# 07_MCU_POWER.net
KiCad netlist of a schematic drawn in Altium Designer
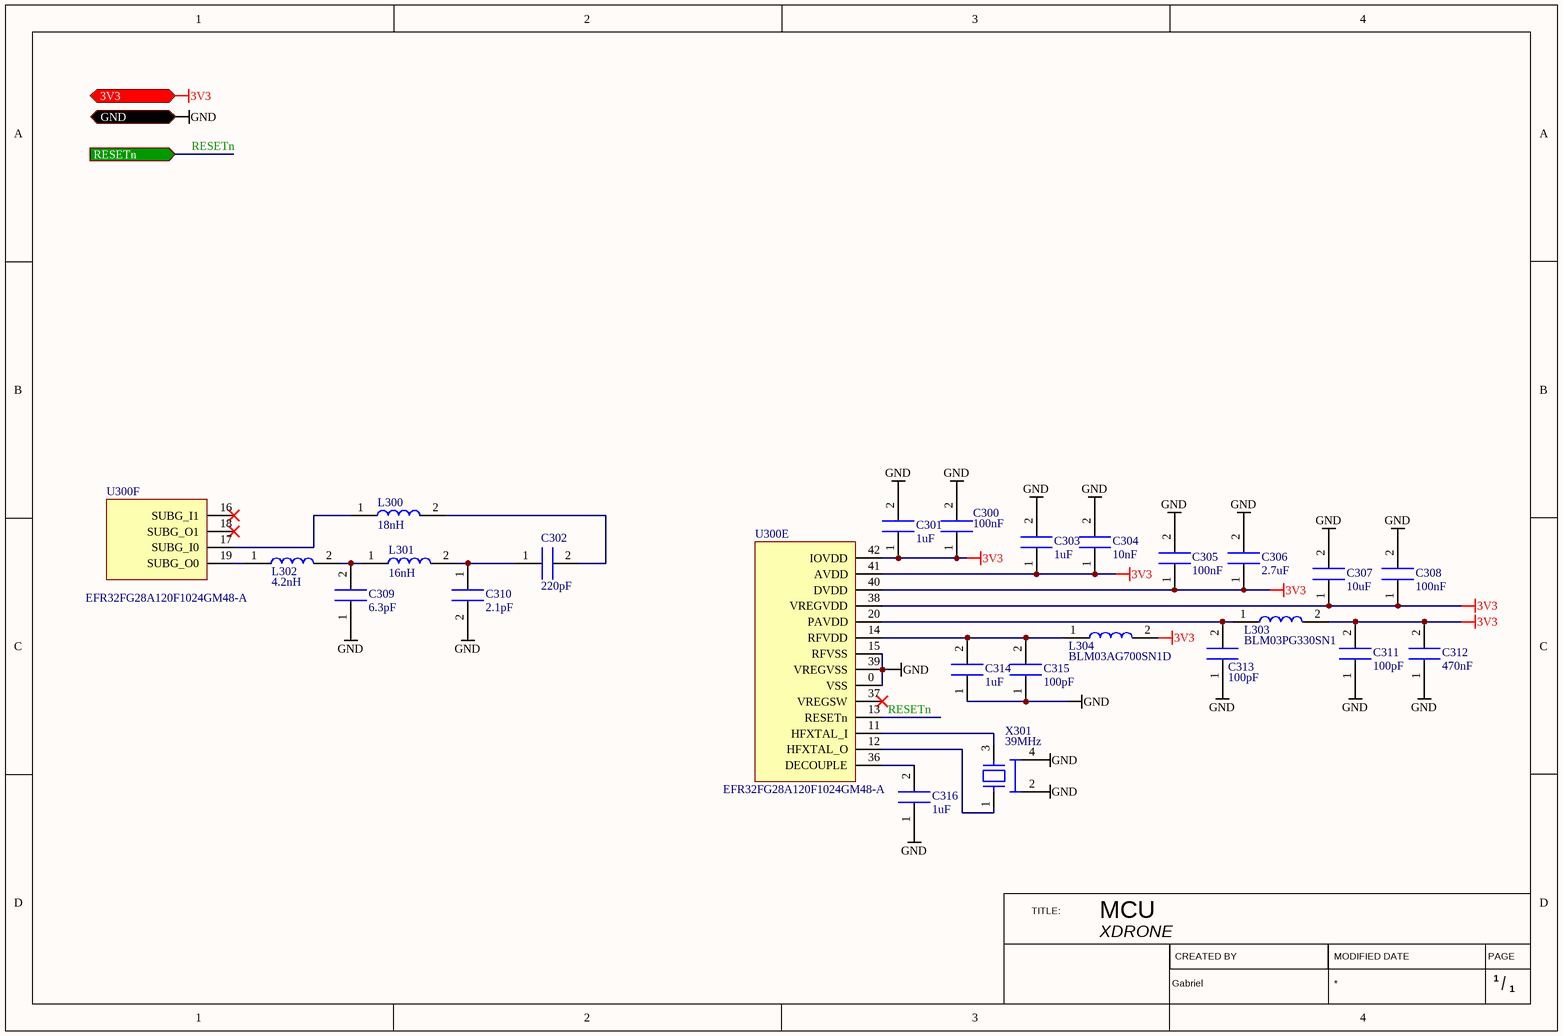
[diagram p0: 07_MCU_POWER.SchDoc]

(export (version "E")
  (design (tool "Eeschema 10.0.6"))
  (components
    (comp (ref "C300")
      (value "100nF")
      (footprint "CAP_0402")
      (description "CAPACITOR 100nF 10% X7R 0402")
      (fields (field (name "TOLERANCE") "10%") (field (name "MANUFACTURER") "MURATA"))
      (libsource (lib "Capacitors") (part "100nF_10%_16V_0402_GRM155R71C104KA88J"))
    )
    (comp (ref "C301")
      (value "1uF")
      (footprint "CAP_0402")
      (description "CAPACITOR 1uF 10% X5R 0402")
      (fields (field (name "TOLERANCE") "10%") (field (name "MANUFACTURER") "MURATA"))
      (libsource (lib "Capacitors") (part "1uF_10%_35V_0402_GRM155R6YA105KE11J"))
    )
    (comp (ref "C302")
      (value "220pF")
      (footprint "CAP_0805")
      (description "CAP 220pF 5% 50V 0805 C0G,NP0")
      (fields (field (name "TOLERANCE") "5%") (field (name "MANUFACTURER") "JOHANSON TECHLONOGY"))
      (libsource (lib "Capacitors") (part "220pF_5%_50V_0805_C0G,NP0_QSCT251Q221J1GV001E"))
    )
    (comp (ref "C303")
      (value "1uF")
      (footprint "CAP_0402")
      (description "CAPACITOR 1uF 10% X5R 0402")
      (fields (field (name "TOLERANCE") "10%") (field (name "MANUFACTURER") "MURATA"))
      (libsource (lib "Capacitors") (part "1uF_10%_35V_0402_GRM155R6YA105KE11J"))
    )
    (comp (ref "C304")
      (value "10nF")
      (footprint "CAP_0402")
      (description "CAPACITOR 10nF 10% 6.3V 0402 CC0402KRX7R5BB103")
      (fields (field (name "TOLERANCE") "10%") (field (name "MANUFACTURER") "YAGEO"))
      (libsource (lib "Capacitors") (part "10nF_10%_6.3V_0402_CC0402KRX7R5BB103"))
    )
    (comp (ref "C305")
      (value "100nF")
      (footprint "CAP_0402")
      (description "CAPACITOR 100nF 10% X7R 0402")
      (fields (field (name "TOLERANCE") "10%") (field (name "MANUFACTURER") "MURATA"))
      (libsource (lib "Capacitors") (part "100nF_10%_16V_0402_GRM155R71C104KA88J"))
    )
    (comp (ref "C306")
      (value "2.7uF")
      (footprint "CAP_0805")
      (description "CAP 2.7uF 10% 10V 0805 X5R C0805C275K8PAC7800")
      (fields (field (name "TOLERANCE") "10%") (field (name "MANUFACTURER") "KEMET"))
      (libsource (lib "Capacitors") (part "2.7uF_10%_10V_0805_X5R_C0805C275K8PAC7800"))
    )
    (comp (ref "C307")
      (value "10uF")
      (footprint "CAP_0402")
      (description "CAPACITOR 10uF 20% 6.3V 0402 GRM155R60J106ME05D")
      (fields (field (name "TOLERANCE") "20%") (field (name "MANUFACTURER") "MURATA"))
      (libsource (lib "Capacitors") (part "10uF 20% 6.3V 0402 GRM155R60J106ME05D"))
    )
    (comp (ref "C308")
      (value "100nF")
      (footprint "CAP_0402")
      (description "CAPACITOR 100nF 10% X7R 0402")
      (fields (field (name "TOLERANCE") "10%") (field (name "MANUFACTURER") "MURATA"))
      (libsource (lib "Capacitors") (part "100nF_10%_16V_0402_GRM155R71C104KA88J"))
    )
    (comp (ref "C309")
      (value "6.3pF")
      (footprint "CAP_0402")
      (description "CAPACITOR 6.3pF 1.5% 50V 0402 CBR04C639B5GAC")
      (fields (field (name "TOLERANCE") "1.5%") (field (name "MANUFACTURER") "KEMET"))
      (libsource (lib "Capacitors") (part "6.3pF_1.5%_50V_0402_CBR04C639B5GAC"))
    )
    (comp (ref "C310")
      (value "2.1pF")
      (footprint "CAP_0402")
      (description "CAPACITOR 2.1pF 5% 50V 0402 GJM1555C1H2R1BB01D")
      (fields (field (name "TOLERANCE") "5%") (field (name "MANUFACTURER") "MURATA"))
      (libsource (lib "Capacitors") (part "2.1pF_5%_50V_0402_GJM1555C1H2R1BB01D"))
    )
    (comp (ref "C311")
      (value "100pF")
      (footprint "CAP_0402")
      (description "CAPACITOR 100pF 5% 50V 0402 CC0402JRNPO9BN101")
      (fields (field (name "TOLERANCE") "5%") (field (name "MANUFACTURER") "YAGEO"))
      (libsource (lib "Capacitors") (part "100pF_5%_50V_0402_CC0402JRNPO9BN101"))
    )
    (comp (ref "C312")
      (value "470nF")
      (footprint "CAP_0402")
      (description "CAPACITOR 470nF 10% 6.3V 0402 GCM1555C1H101JA16D")
      (fields (field (name "TOLERANCE") "5%") (field (name "MANUFACTURER") "MURATA"))
      (libsource (lib "Capacitors") (part "470nF_10%_6.3V_0402_GCM1555C1H101JA16D"))
    )
    (comp (ref "C313")
      (value "100pF")
      (footprint "CAP_0402")
      (description "CAPACITOR 100pF 5% 50V 0402 CC0402JRNPO9BN101")
      (fields (field (name "TOLERANCE") "5%") (field (name "MANUFACTURER") "YAGEO"))
      (libsource (lib "Capacitors") (part "100pF_5%_50V_0402_CC0402JRNPO9BN101"))
    )
    (comp (ref "C314")
      (value "1uF")
      (footprint "CAP_0402")
      (description "CAPACITOR 1uF 10% X5R 0402")
      (fields (field (name "TOLERANCE") "10%") (field (name "MANUFACTURER") "MURATA"))
      (libsource (lib "Capacitors") (part "1uF_10%_35V_0402_GRM155R6YA105KE11J"))
    )
    (comp (ref "C315")
      (value "100pF")
      (footprint "CAP_0402")
      (description "CAPACITOR 100pF 5% 50V 0402 CC0402JRNPO9BN101")
      (fields (field (name "TOLERANCE") "5%") (field (name "MANUFACTURER") "YAGEO"))
      (libsource (lib "Capacitors") (part "100pF_5%_50V_0402_CC0402JRNPO9BN101"))
    )
    (comp (ref "C316")
      (value "1uF")
      (footprint "CAP_0402")
      (description "CAPACITOR 1uF 10% X5R 0402")
      (fields (field (name "TOLERANCE") "10%") (field (name "MANUFACTURER") "MURATA"))
      (libsource (lib "Capacitors") (part "1uF_10%_35V_0402_GRM155R6YA105KE11J"))
    )
    (comp (ref "L300")
      (value "18nH")
      (footprint "RF_IND_0402")
      (description "INDUCTOR 18nH 2% 400mA LQG15HS18NG02D")
      (fields (field (name "TOLERANCE") "2%") (field (name "MANUFACTURER") "MURATA"))
      (libsource (lib "Inductors") (part "18nH_2%_400mA_LQG15HS18NG02D"))
    )
    (comp (ref "L301")
      (value "16nH")
      (footprint "RF_IND_0402")
      (description "INDUCTOR 16nH 3% 400mA MLG1005S16NHT000")
      (fields (field (name "TOLERANCE") "3%") (field (name "MANUFACTURER") "TDK"))
      (libsource (lib "Inductors") (part "16nH_3%_400mA_MLG1005S16NHT000"))
    )
    (comp (ref "L302")
      (value "4.2nH")
      (footprint "RF_IND_0402")
      (description "INDUCTOR 4.2nH 5% 1.8A LQW15AN4N2C8ZD")
      (fields (field (name "TOLERANCE") "5%") (field (name "MANUFACTURER") "MURATA"))
      (libsource (lib "Inductors") (part "4.2nH_5%_1.8A_LQW15AN4N2C8ZD"))
    )
    (comp (ref "L303")
      (value "52nH_25%_750mA_BLM03PG330SN1")
      (footprint "IND_0201")
      (description "INDUCTOR 52uH 25% 750mA BLM03PG330SN1")
      (fields
        (field (name "TOLERANCE") "25%")
        (field (name "MANUFACTURER") "MURATA")
        (field (name "MANUFACTURER REFERENCE") "BLM03PG330SN1")
      )
      (libsource (lib "Inductors") (part "52nH_25%_750mA_BLM03PG330SN1"))
    )
    (comp (ref "L304")
      (value "110nH_50%_200mA_BLM03AG700SN1D")
      (footprint "IND_0201")
      (description "INDUCTOR 110nH 50% 200mA BLM03AG700SN1D")
      (fields
        (field (name "TOLERANCE") "50%")
        (field (name "MANUFACTURER") "MURATA")
        (field (name "MANUFACTURER REFERENCE") "BLM03AG700SN1D")
      )
      (libsource (lib "Inductors") (part "110nH 50% 200mA BLM03AG700SN1D"))
    )
    (comp (ref "U300")
      (value "MCU_1MB_256kB_EFR32FG28A120F1024GM48-A")
      (footprint "QFN48 0606")
      (description "MCU 1MB 256kB EFR32FG28A120F1024GM48-A")
      (fields
        (field (name "MANUFACTURER") "SILICON LABS")
        (field (name "MANUFACTURER REFERENCE") "EFR32FG28A120F1024GM48-A")
      )
      (libsource (lib "Semiconductor") (part "MCU_1MB_256kB_EFR32FG28A120F1024GM48-A"))
    )
    (comp (ref "X301")
      (value "QUARTZ_39MHz_10ppm_ECS-390-10-37B-CKM-TR")
      (footprint "QUARTZ_4-SMD")
      (description "QUARTZ 39MHz 10ppm ECS-390-10-37B-CKM-TR")
      (fields
        (field (name "MANUFACTURER") "ECS")
        (field (name "TOLERANCE") "10 ppm")
        (field (name "FREQUENCY") "39MHz")
      )
      (libsource (lib "Oscillators") (part "QUARTZ_39MHz_10ppm_ECS-390-10-37B-CKM-TR"))
    )
  )
  (nets
    (net (code "1") (name "/RESETn") (class "Default")
      (node (ref "U300") (pin "13") (pinfunction "RESETn_13") (pintype "passive"))
    )
    (net (code "2") (name "3V3") (class "Default")
      (node (ref "C300") (pin "1") (pinfunction "1_1") (pintype "passive"))
      (node (ref "C301") (pin "1") (pinfunction "1_1") (pintype "passive"))
      (node (ref "C303") (pin "1") (pinfunction "1_1") (pintype "passive"))
      (node (ref "C304") (pin "1") (pinfunction "1_1") (pintype "passive"))
      (node (ref "C305") (pin "1") (pinfunction "1_1") (pintype "passive"))
      (node (ref "C306") (pin "1") (pinfunction "1_1") (pintype "passive"))
      (node (ref "C307") (pin "1") (pinfunction "1_1") (pintype "passive"))
      (node (ref "C308") (pin "1") (pinfunction "1_1") (pintype "passive"))
      (node (ref "C311") (pin "2") (pinfunction "2_2") (pintype "passive"))
      (node (ref "C312") (pin "2") (pinfunction "2_2") (pintype "passive"))
      (node (ref "L303") (pin "2") (pinfunction "2_2") (pintype "passive"))
      (node (ref "L304") (pin "2") (pinfunction "2_2") (pintype "passive"))
      (node (ref "U300") (pin "38") (pinfunction "VREGVDD_38") (pintype "passive"))
      (node (ref "U300") (pin "40") (pinfunction "DVDD_40") (pintype "passive"))
      (node (ref "U300") (pin "41") (pinfunction "AVDD_41") (pintype "passive"))
      (node (ref "U300") (pin "42") (pinfunction "IOVDD_42") (pintype "passive"))
    )
    (net (code "3") (name "GND") (class "Default")
      (node (ref "C300") (pin "2") (pinfunction "2_2") (pintype "passive"))
      (node (ref "C301") (pin "2") (pinfunction "2_2") (pintype "passive"))
      (node (ref "C303") (pin "2") (pinfunction "2_2") (pintype "passive"))
      (node (ref "C304") (pin "2") (pinfunction "2_2") (pintype "passive"))
      (node (ref "C305") (pin "2") (pinfunction "2_2") (pintype "passive"))
      (node (ref "C306") (pin "2") (pinfunction "2_2") (pintype "passive"))
      (node (ref "C307") (pin "2") (pinfunction "2_2") (pintype "passive"))
      (node (ref "C308") (pin "2") (pinfunction "2_2") (pintype "passive"))
      (node (ref "C309") (pin "1") (pinfunction "1_1") (pintype "passive"))
      (node (ref "C310") (pin "2") (pinfunction "2_2") (pintype "passive"))
      (node (ref "C311") (pin "1") (pinfunction "1_1") (pintype "passive"))
      (node (ref "C312") (pin "1") (pinfunction "1_1") (pintype "passive"))
      (node (ref "C313") (pin "1") (pinfunction "1_1") (pintype "passive"))
      (node (ref "C314") (pin "1") (pinfunction "1_1") (pintype "passive"))
      (node (ref "C315") (pin "1") (pinfunction "1_1") (pintype "passive"))
      (node (ref "C316") (pin "1") (pinfunction "1_1") (pintype "passive"))
      (node (ref "U300") (pin "0") (pinfunction "VSS_0") (pintype "passive"))
      (node (ref "U300") (pin "15") (pinfunction "RFVSS_15") (pintype "passive"))
      (node (ref "U300") (pin "39") (pinfunction "VREGVSS_39") (pintype "passive"))
      (node (ref "X301") (pin "2") (pinfunction "2_2") (pintype "passive"))
      (node (ref "X301") (pin "4") (pinfunction "4_4") (pintype "passive"))
    )
    (net (code "4") (name "Net-(C302-Pad1)") (class "Default")
      (node (ref "C302") (pin "1") (pinfunction "1_1") (pintype "passive"))
      (node (ref "C310") (pin "1") (pinfunction "1_1") (pintype "passive"))
      (node (ref "L301") (pin "2") (pinfunction "2_2") (pintype "passive"))
    )
    (net (code "5") (name "Net-(C302-Pad2)") (class "Default")
      (node (ref "C302") (pin "2") (pinfunction "2_2") (pintype "passive"))
      (node (ref "L300") (pin "2") (pinfunction "2_2") (pintype "passive"))
    )
    (net (code "6") (name "Net-(C309-Pad2)") (class "Default")
      (node (ref "C309") (pin "2") (pinfunction "2_2") (pintype "passive"))
      (node (ref "L301") (pin "1") (pinfunction "1_1") (pintype "passive"))
      (node (ref "L302") (pin "2") (pinfunction "2_2") (pintype "passive"))
    )
    (net (code "7") (name "Net-(U300E-DECOUPLE)") (class "Default")
      (node (ref "C316") (pin "2") (pinfunction "2_2") (pintype "passive"))
      (node (ref "U300") (pin "36") (pinfunction "DECOUPLE_36") (pintype "passive"))
    )
    (net (code "8") (name "Net-(U300E-HFXTAL_I)") (class "Default")
      (node (ref "U300") (pin "11") (pinfunction "HFXTAL_I_11") (pintype "passive"))
      (node (ref "X301") (pin "3") (pinfunction "3_3") (pintype "passive"))
    )
    (net (code "9") (name "Net-(U300E-HFXTAL_O)") (class "Default")
      (node (ref "U300") (pin "12") (pinfunction "HFXTAL_O_12") (pintype "passive"))
      (node (ref "X301") (pin "1") (pinfunction "1_1") (pintype "passive"))
    )
    (net (code "10") (name "Net-(U300E-PAVDD)") (class "Default")
      (node (ref "C313") (pin "2") (pinfunction "2_2") (pintype "passive"))
      (node (ref "L303") (pin "1") (pinfunction "1_1") (pintype "passive"))
      (node (ref "U300") (pin "20") (pinfunction "PAVDD_20") (pintype "passive"))
    )
    (net (code "11") (name "Net-(U300E-RFVDD)") (class "Default")
      (node (ref "C314") (pin "2") (pinfunction "2_2") (pintype "passive"))
      (node (ref "C315") (pin "2") (pinfunction "2_2") (pintype "passive"))
      (node (ref "L304") (pin "1") (pinfunction "1_1") (pintype "passive"))
      (node (ref "U300") (pin "14") (pinfunction "RFVDD_14") (pintype "passive"))
    )
    (net (code "12") (name "Net-(U300F-SUBG_I0)") (class "Default")
      (node (ref "L300") (pin "1") (pinfunction "1_1") (pintype "passive"))
      (node (ref "U300") (pin "17") (pinfunction "SUBG_I0_17") (pintype "passive"))
    )
    (net (code "13") (name "Net-(U300F-SUBG_O0)") (class "Default")
      (node (ref "L302") (pin "1") (pinfunction "1_1") (pintype "passive"))
      (node (ref "U300") (pin "19") (pinfunction "SUBG_O0_19") (pintype "passive"))
    )
    (net (code "14") (name "unconnected-(U300E-VREGSW-Pad37)") (class "Default")
      (node (ref "U300") (pin "37") (pinfunction "VREGSW_37") (pintype "passive+no_connect"))
    )
    (net (code "15") (name "unconnected-(U300F-SUBG_I1-Pad16)") (class "Default")
      (node (ref "U300") (pin "16") (pinfunction "SUBG_I1_16") (pintype "passive+no_connect"))
    )
    (net (code "16") (name "unconnected-(U300F-SUBG_O1-Pad18)") (class "Default")
      (node (ref "U300") (pin "18") (pinfunction "SUBG_O1_18") (pintype "passive+no_connect"))
    )
  )
)
